# MIDI_Breakout.net
KiCad netlist of a schematic drawn in EAGLE
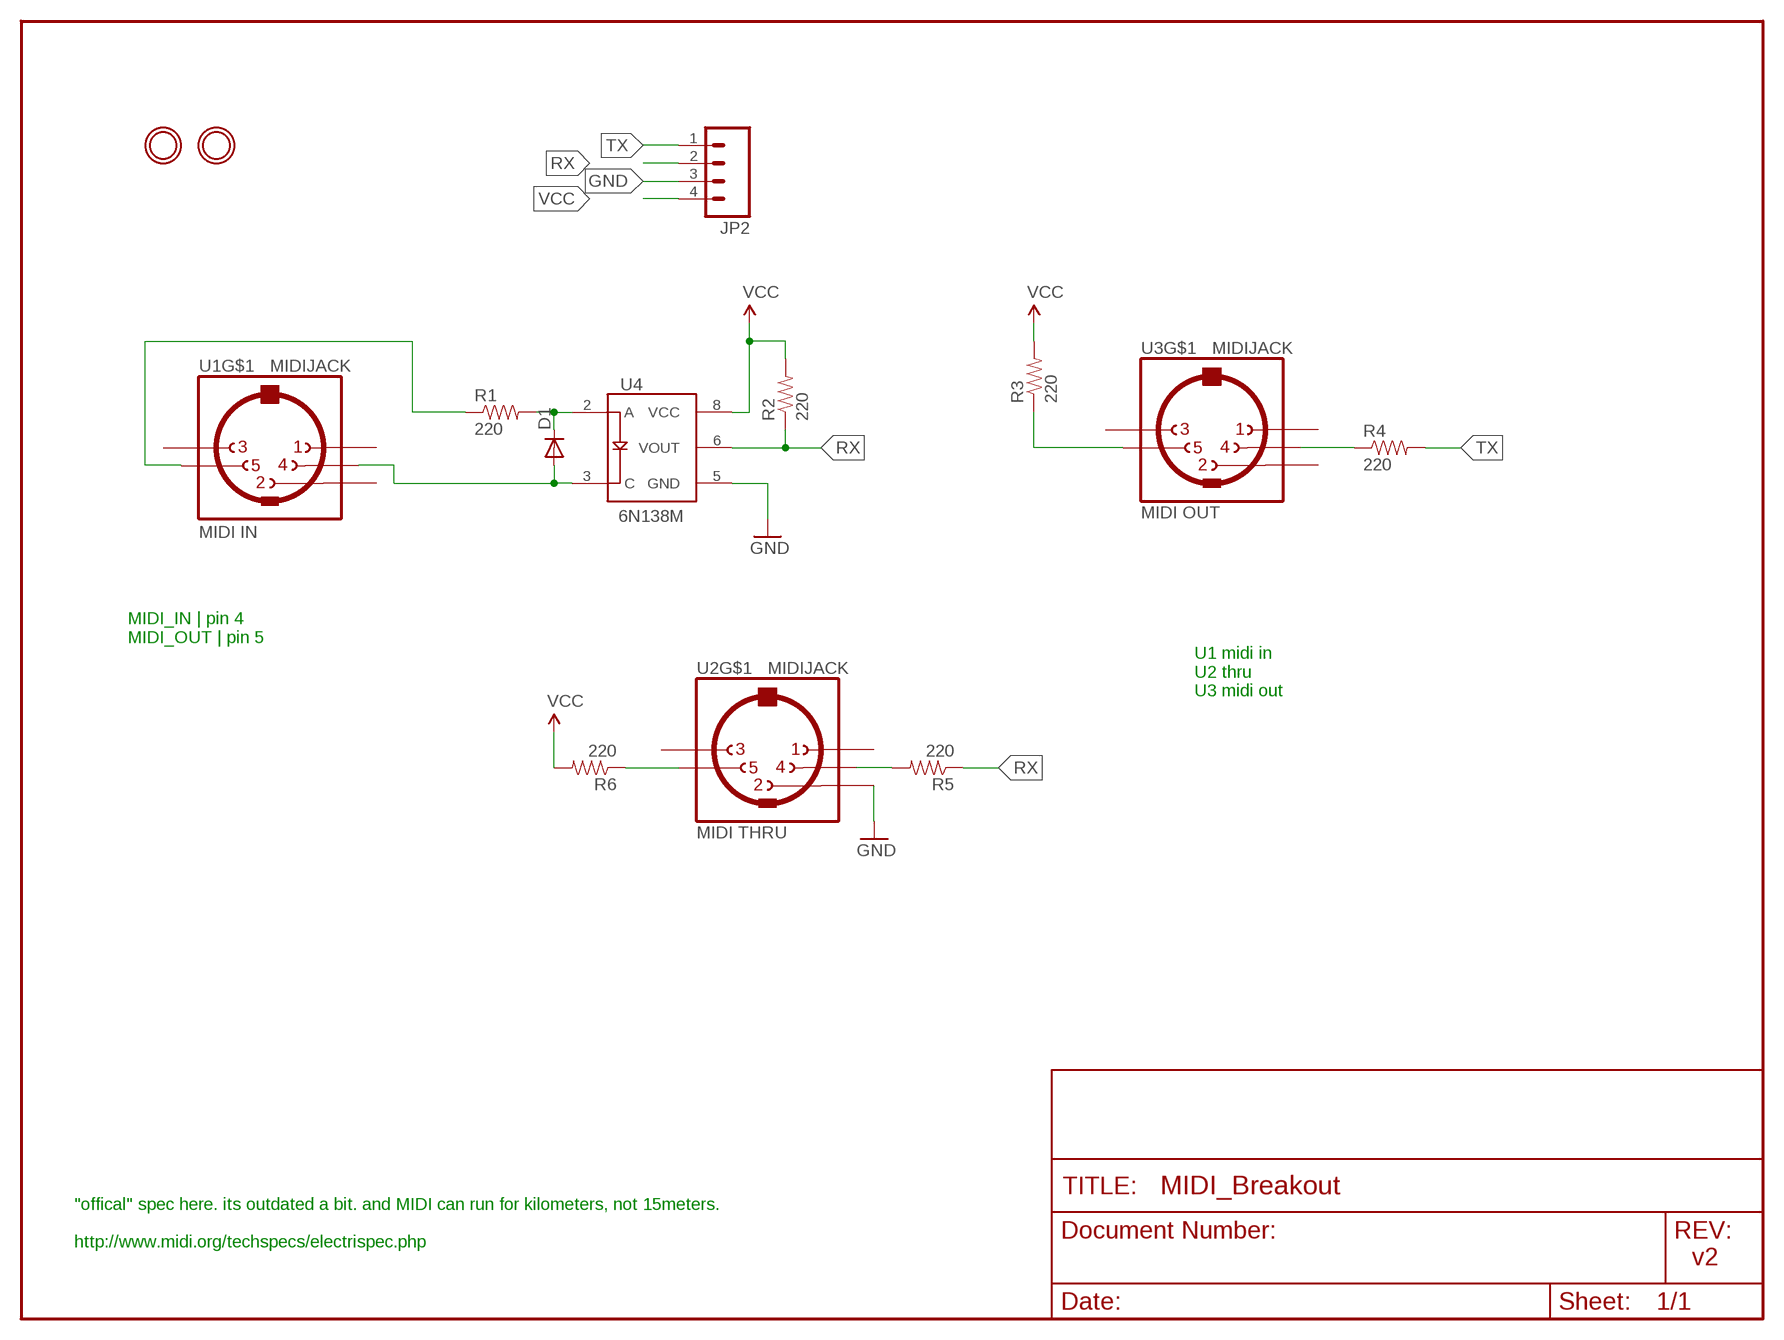
[diagram p0: schematic, sheet 1]

(export (version "E")
  (design (tool "Eeschema 10.0.6"))
  (components
    (comp (ref "D1")
      (value "DIODESMA")
      (footprint "eagle-import:SMA-DIODE")
      (libsource (lib "eagle-import") (part "DIODESMA"))
    )
    (comp (ref "JP2")
      (value "M041X04_NO_SILK")
      (footprint "eagle-import:1X04_NO_SILK")
      (libsource (lib "eagle-import") (part "M041X04_NO_SILK"))
    )
    (comp (ref "R1")
      (value "220")
      (footprint "eagle-import:AXIAL-0.5")
      (libsource (lib "eagle-import") (part "RESISTORPTH-1/2W"))
    )
    (comp (ref "R2")
      (value "220")
      (footprint "eagle-import:AXIAL-0.5")
      (libsource (lib "eagle-import") (part "RESISTORPTH-1/2W"))
    )
    (comp (ref "R3")
      (value "220")
      (footprint "eagle-import:AXIAL-0.5")
      (libsource (lib "eagle-import") (part "RESISTORPTH-1/2W"))
    )
    (comp (ref "R4")
      (value "220")
      (footprint "eagle-import:AXIAL-0.5")
      (libsource (lib "eagle-import") (part "RESISTORPTH-1/2W"))
    )
    (comp (ref "R5")
      (value "220")
      (footprint "eagle-import:AXIAL-0.5")
      (libsource (lib "eagle-import") (part "RESISTORPTH-1/2W"))
    )
    (comp (ref "R6")
      (value "220")
      (footprint "eagle-import:AXIAL-0.5")
      (libsource (lib "eagle-import") (part "RESISTORPTH-1/2W"))
    )
    (comp (ref "U$1")
      (value "MOUNTINGHOLE")
      (footprint "eagle-import:MOUNTINGHOLE_3.0_PLATED")
      (libsource (lib "eagle-import") (part "MOUNTINGHOLE"))
    )
    (comp (ref "U$2")
      (value "MOUNTINGHOLE")
      (footprint "eagle-import:MOUNTINGHOLE_3.0_PLATED")
      (libsource (lib "eagle-import") (part "MOUNTINGHOLE"))
    )
    (comp (ref "U1")
      (value "MIDIJACK")
      (footprint "eagle-import:CP-2350")
      (libsource (lib "eagle-import") (part "MIDIJACK"))
    )
    (comp (ref "U2")
      (value "MIDIJACK")
      (footprint "eagle-import:CP-2350")
      (libsource (lib "eagle-import") (part "MIDIJACK"))
    )
    (comp (ref "U3")
      (value "MIDIJACK")
      (footprint "eagle-import:CP-2350")
      (libsource (lib "eagle-import") (part "MIDIJACK"))
    )
    (comp (ref "U4")
      (value "6N138M")
      (footprint "eagle-import:8-SMD")
      (libsource (lib "eagle-import") (part "OPTO_DARL_6N138S"))
    )
  )
  (nets
    (net (code "1") (name "GND") (class "Default")
      (node (ref "JP2") (pin "3") (pinfunction "3_3") (pintype "passive"))
      (node (ref "U2") (pin "2") (pinfunction "2_2") (pintype "passive"))
      (node (ref "U4") (pin "5") (pinfunction "GND_5") (pintype "bidirectional"))
    )
    (net (code "2") (name "Net-(R1-1)") (class "Default")
      (node (ref "R1") (pin "P$1") (pinfunction "1_P$1") (pintype "passive"))
      (node (ref "U1") (pin "5") (pinfunction "5_5") (pintype "passive"))
    )
    (net (code "3") (name "Net-(R1-2)") (class "Default")
      (node (ref "D1") (pin "C") (pinfunction "C_C") (pintype "passive"))
      (node (ref "R1") (pin "P$2") (pinfunction "2_P$2") (pintype "passive"))
      (node (ref "U4") (pin "2") (pinfunction "A_2") (pintype "bidirectional"))
    )
    (net (code "4") (name "Net-(R3-1)") (class "Default")
      (node (ref "R3") (pin "P$1") (pinfunction "1_P$1") (pintype "passive"))
      (node (ref "U3") (pin "5") (pinfunction "5_5") (pintype "passive"))
    )
    (net (code "5") (name "Net-(R4-1)") (class "Default")
      (node (ref "R4") (pin "P$1") (pinfunction "1_P$1") (pintype "passive"))
      (node (ref "U3") (pin "4") (pinfunction "4_4") (pintype "passive"))
    )
    (net (code "6") (name "Net-(R5-2)") (class "Default")
      (node (ref "R5") (pin "P$2") (pinfunction "2_P$2") (pintype "passive"))
      (node (ref "U2") (pin "4") (pinfunction "4_4") (pintype "passive"))
    )
    (net (code "7") (name "Net-(R6-1)") (class "Default")
      (node (ref "R6") (pin "P$1") (pinfunction "1_P$1") (pintype "passive"))
      (node (ref "U2") (pin "5") (pinfunction "5_5") (pintype "passive"))
    )
    (net (code "8") (name "Net-(U4-C)") (class "Default")
      (node (ref "D1") (pin "A") (pinfunction "A_A") (pintype "passive"))
      (node (ref "U1") (pin "4") (pinfunction "4_4") (pintype "passive"))
      (node (ref "U4") (pin "3") (pinfunction "C_3") (pintype "bidirectional"))
    )
    (net (code "9") (name "RX") (class "Default")
      (node (ref "JP2") (pin "2") (pinfunction "2_2") (pintype "passive"))
      (node (ref "R2") (pin "P$1") (pinfunction "1_P$1") (pintype "passive"))
      (node (ref "R5") (pin "P$1") (pinfunction "1_P$1") (pintype "passive"))
      (node (ref "U4") (pin "6") (pinfunction "VOUT_6") (pintype "bidirectional"))
    )
    (net (code "10") (name "TX") (class "Default")
      (node (ref "JP2") (pin "1") (pinfunction "1_1") (pintype "passive"))
      (node (ref "R4") (pin "P$2") (pinfunction "2_P$2") (pintype "passive"))
    )
    (net (code "11") (name "VCC") (class "Default")
      (node (ref "JP2") (pin "4") (pinfunction "4_4") (pintype "passive"))
      (node (ref "R2") (pin "P$2") (pinfunction "2_P$2") (pintype "passive"))
      (node (ref "R3") (pin "P$2") (pinfunction "2_P$2") (pintype "passive"))
      (node (ref "R6") (pin "P$2") (pinfunction "2_P$2") (pintype "passive"))
      (node (ref "U4") (pin "8") (pinfunction "VCC_8") (pintype "bidirectional"))
    )
    (net (code "12") (name "unconnected-(U1-Pad1)") (class "Default")
      (node (ref "U1") (pin "1") (pinfunction "1_1") (pintype "passive"))
    )
    (net (code "13") (name "unconnected-(U1-Pad2)") (class "Default")
      (node (ref "U1") (pin "2") (pinfunction "2_2") (pintype "passive"))
    )
    (net (code "14") (name "unconnected-(U1-Pad3)") (class "Default")
      (node (ref "U1") (pin "3") (pinfunction "3_3") (pintype "passive"))
    )
    (net (code "15") (name "unconnected-(U2-Pad1)") (class "Default")
      (node (ref "U2") (pin "1") (pinfunction "1_1") (pintype "passive"))
    )
    (net (code "16") (name "unconnected-(U2-Pad3)") (class "Default")
      (node (ref "U2") (pin "3") (pinfunction "3_3") (pintype "passive"))
    )
    (net (code "17") (name "unconnected-(U3-Pad1)") (class "Default")
      (node (ref "U3") (pin "1") (pinfunction "1_1") (pintype "passive"))
    )
    (net (code "18") (name "unconnected-(U3-Pad2)") (class "Default")
      (node (ref "U3") (pin "2") (pinfunction "2_2") (pintype "passive"))
    )
    (net (code "19") (name "unconnected-(U3-Pad3)") (class "Default")
      (node (ref "U3") (pin "3") (pinfunction "3_3") (pintype "passive"))
    )
  )
)
